# Thermocouple.net
KiCad netlist of a schematic drawn in Altium Designer
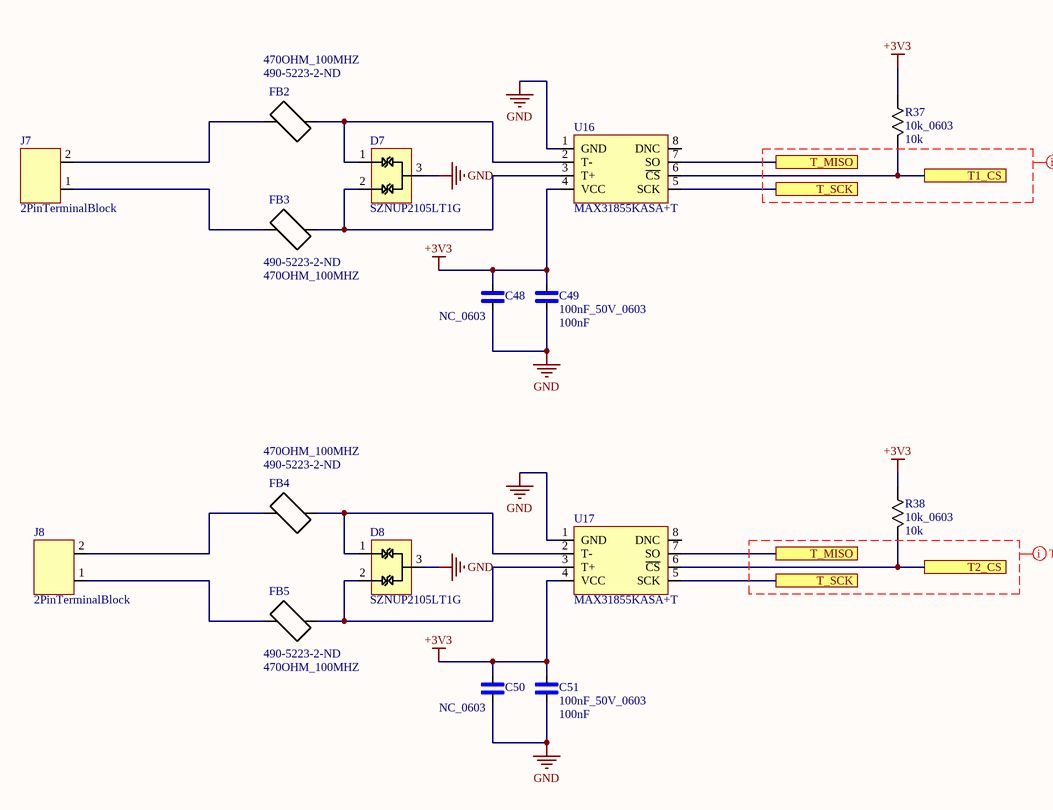
[diagram p0: Thermocouple.SchDoc]

(export (version "E")
  (design (tool "Eeschema 10.0.6"))
  (components
    (comp (ref "C48") (value "NC_0603") (footprint "0603") (libsource (lib "Capacitors") (part "NC_0603")))
    (comp (ref "C49")
      (value "100nF_50V_0603")
      (footprint "0603")
      (fields
        (field (name "MANUFACTURER") "Murata")
        (field (name "MANUFACTURER PART NUMBER") "GRM188R71H104KA93D")
        (field (name "TOLERANCE") "10%")
        (field (name "CAPACITANCE") "100nF")
      )
      (libsource (lib "Capacitors") (part "100nF_50V_0603"))
    )
    (comp (ref "C50") (value "NC_0603") (footprint "0603") (libsource (lib "Capacitors") (part "NC_0603")))
    (comp (ref "C51")
      (value "100nF_50V_0603")
      (footprint "0603")
      (fields
        (field (name "MANUFACTURER") "Murata")
        (field (name "MANUFACTURER PART NUMBER") "GRM188R71H104KA93D")
        (field (name "TOLERANCE") "10%")
        (field (name "CAPACITANCE") "100nF")
      )
      (libsource (lib "Capacitors") (part "100nF_50V_0603"))
    )
    (comp (ref "D7")
      (value "SZNUP2105LT1G")
      (footprint "SOT-23-3")
      (libsource (lib "Diodes") (part "SZNUP2105LT1G"))
    )
    (comp (ref "D8")
      (value "SZNUP2105LT1G")
      (footprint "SOT-23-3")
      (libsource (lib "Diodes") (part "SZNUP2105LT1G"))
    )
    (comp (ref "FB2")
      (value "470OHM_100MHZ")
      (footprint "0603")
      (fields
        (field (name "MANUFACTURER") "Murata")
        (field (name "MANUFACTURER PART NUMBER") "BLM18PG471SN1D")
        (field (name "TOLERANCE") "25%")
        (field (name "SUPPLIER PART NUMBER 1") "490-5223-2-ND")
      )
      (libsource (lib "FerriteBeads") (part "470OHM_100MHZ"))
    )
    (comp (ref "FB3")
      (value "470OHM_100MHZ")
      (footprint "0603")
      (fields
        (field (name "MANUFACTURER") "Murata")
        (field (name "MANUFACTURER PART NUMBER") "BLM18PG471SN1D")
        (field (name "TOLERANCE") "25%")
        (field (name "SUPPLIER PART NUMBER 1") "490-5223-2-ND")
      )
      (libsource (lib "FerriteBeads") (part "470OHM_100MHZ"))
    )
    (comp (ref "FB4")
      (value "470OHM_100MHZ")
      (footprint "0603")
      (fields
        (field (name "MANUFACTURER") "Murata")
        (field (name "MANUFACTURER PART NUMBER") "BLM18PG471SN1D")
        (field (name "TOLERANCE") "25%")
        (field (name "SUPPLIER PART NUMBER 1") "490-5223-2-ND")
      )
      (libsource (lib "FerriteBeads") (part "470OHM_100MHZ"))
    )
    (comp (ref "FB5")
      (value "470OHM_100MHZ")
      (footprint "0603")
      (fields
        (field (name "MANUFACTURER") "Murata")
        (field (name "MANUFACTURER PART NUMBER") "BLM18PG471SN1D")
        (field (name "TOLERANCE") "25%")
        (field (name "SUPPLIER PART NUMBER 1") "490-5223-2-ND")
      )
      (libsource (lib "FerriteBeads") (part "470OHM_100MHZ"))
    )
    (comp (ref "J7")
      (value "2PinTerminalBlock")
      (footprint "2 Pos 2.54mm Pitch")
      (description "2.54mm Terminal Connector")
      (libsource (lib "Connectors") (part "2PinTerminalBlock"))
    )
    (comp (ref "J8")
      (value "2PinTerminalBlock")
      (footprint "2 Pos 2.54mm Pitch")
      (description "2.54mm Terminal Connector")
      (libsource (lib "Connectors") (part "2PinTerminalBlock"))
    )
    (comp (ref "R37")
      (value "10k_0603")
      (footprint "0603")
      (fields
        (field (name "MANUFACTURER") "Panasonic")
        (field (name "MANUFACTURER PART NUMBER") "ERJ-3EKF1002V")
        (field (name "TOLERANCE") "1%")
        (field (name "RESISTANCE") "10k")
      )
      (libsource (lib "Resistors") (part "10k_0603"))
    )
    (comp (ref "R38")
      (value "10k_0603")
      (footprint "0603")
      (fields
        (field (name "MANUFACTURER") "Panasonic")
        (field (name "MANUFACTURER PART NUMBER") "ERJ-3EKF1002V")
        (field (name "TOLERANCE") "1%")
        (field (name "RESISTANCE") "10k")
      )
      (libsource (lib "Resistors") (part "10k_0603"))
    )
    (comp (ref "U16")
      (value "MAX31855KASA+T")
      (footprint "MAX31855KASA+T")
      (description "K type thermocouple amplifier")
      (libsource (lib "MiscComponents") (part "MAX31855KASA+T"))
    )
    (comp (ref "U17")
      (value "MAX31855KASA+T")
      (footprint "MAX31855KASA+T")
      (description "K type thermocouple amplifier")
      (libsource (lib "MiscComponents") (part "MAX31855KASA+T"))
    )
  )
  (nets
    (net (code "1") (name "+3V3") (class "Default")
      (node (ref "C48") (pin "2") (pinfunction "2_2") (pintype "passive"))
      (node (ref "C49") (pin "2") (pinfunction "2_2") (pintype "passive"))
      (node (ref "C50") (pin "2") (pinfunction "2_2") (pintype "passive"))
      (node (ref "C51") (pin "2") (pinfunction "2_2") (pintype "passive"))
      (node (ref "R37") (pin "2") (pinfunction "2_2") (pintype "passive"))
      (node (ref "R38") (pin "2") (pinfunction "2_2") (pintype "passive"))
      (node (ref "U16") (pin "4") (pinfunction "VCC_4") (pintype "passive"))
      (node (ref "U17") (pin "4") (pinfunction "VCC_4") (pintype "passive"))
    )
    (net (code "2") (name "/T1_CS") (class "Default")
      (node (ref "R37") (pin "1") (pinfunction "1_1") (pintype "passive"))
      (node (ref "U16") (pin "6") (pinfunction "~{CS}_6") (pintype "passive"))
    )
    (net (code "3") (name "/T2_CS") (class "Default")
      (node (ref "R38") (pin "1") (pinfunction "1_1") (pintype "passive"))
      (node (ref "U17") (pin "6") (pinfunction "~{CS}_6") (pintype "passive"))
    )
    (net (code "4") (name "/T_MISO") (class "Default")
      (node (ref "U16") (pin "7") (pinfunction "SO_7") (pintype "passive"))
      (node (ref "U17") (pin "7") (pinfunction "SO_7") (pintype "passive"))
    )
    (net (code "5") (name "/T_SCK") (class "Default")
      (node (ref "U16") (pin "5") (pinfunction "SCK_5") (pintype "passive"))
      (node (ref "U17") (pin "5") (pinfunction "SCK_5") (pintype "passive"))
    )
    (net (code "6") (name "GND") (class "Default")
      (node (ref "C48") (pin "1") (pinfunction "1_1") (pintype "passive"))
      (node (ref "C49") (pin "1") (pinfunction "1_1") (pintype "passive"))
      (node (ref "C50") (pin "1") (pinfunction "1_1") (pintype "passive"))
      (node (ref "C51") (pin "1") (pinfunction "1_1") (pintype "passive"))
      (node (ref "D7") (pin "3") (pinfunction "3_3") (pintype "passive"))
      (node (ref "D8") (pin "3") (pinfunction "3_3") (pintype "passive"))
      (node (ref "U16") (pin "1") (pinfunction "GND_1") (pintype "passive"))
      (node (ref "U17") (pin "1") (pinfunction "GND_1") (pintype "passive"))
    )
    (net (code "7") (name "Net-(FB2-Pad1)") (class "Default")
      (node (ref "FB2") (pin "1") (pintype "passive"))
      (node (ref "J7") (pin "2") (pintype "passive"))
    )
    (net (code "8") (name "Net-(FB3-Pad1)") (class "Default")
      (node (ref "FB3") (pin "1") (pintype "passive"))
      (node (ref "J7") (pin "1") (pintype "passive"))
    )
    (net (code "9") (name "Net-(FB4-Pad1)") (class "Default")
      (node (ref "FB4") (pin "1") (pintype "passive"))
      (node (ref "J8") (pin "2") (pintype "passive"))
    )
    (net (code "10") (name "Net-(FB5-Pad1)") (class "Default")
      (node (ref "FB5") (pin "1") (pintype "passive"))
      (node (ref "J8") (pin "1") (pintype "passive"))
    )
    (net (code "11") (name "Net-(U16-T+)") (class "Default")
      (node (ref "D7") (pin "2") (pinfunction "2_2") (pintype "passive"))
      (node (ref "FB3") (pin "2") (pintype "passive"))
      (node (ref "U16") (pin "3") (pinfunction "T+_3") (pintype "passive"))
    )
    (net (code "12") (name "Net-(U16-T-)") (class "Default")
      (node (ref "D7") (pin "1") (pinfunction "1_1") (pintype "passive"))
      (node (ref "FB2") (pin "2") (pintype "passive"))
      (node (ref "U16") (pin "2") (pinfunction "T-_2") (pintype "passive"))
    )
    (net (code "13") (name "Net-(U17-T+)") (class "Default")
      (node (ref "D8") (pin "2") (pinfunction "2_2") (pintype "passive"))
      (node (ref "FB5") (pin "2") (pintype "passive"))
      (node (ref "U17") (pin "3") (pinfunction "T+_3") (pintype "passive"))
    )
    (net (code "14") (name "Net-(U17-T-)") (class "Default")
      (node (ref "D8") (pin "1") (pinfunction "1_1") (pintype "passive"))
      (node (ref "FB4") (pin "2") (pintype "passive"))
      (node (ref "U17") (pin "2") (pinfunction "T-_2") (pintype "passive"))
    )
    (net (code "15") (name "unconnected-(U16-DNC-Pad8)") (class "Default")
      (node (ref "U16") (pin "8") (pinfunction "DNC_8") (pintype "passive"))
    )
    (net (code "16") (name "unconnected-(U17-DNC-Pad8)") (class "Default")
      (node (ref "U17") (pin "8") (pinfunction "DNC_8") (pintype "passive"))
    )
  )
)
